# 7_Halleffec.net
KiCad netlist of a schematic drawn in Altium Designer
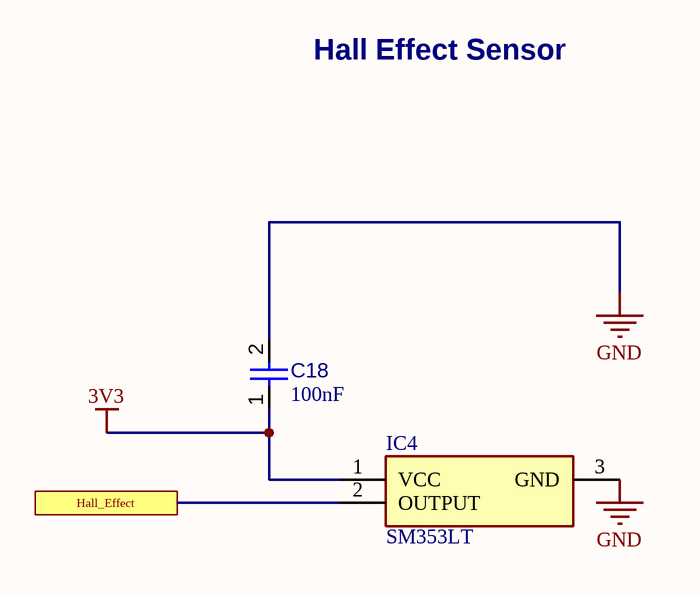
[diagram p0: [7]Halleffec.SchDoc]

(export (version "E")
  (design (tool "Eeschema 10.0.6"))
  (components
    (comp (ref "C18")
      (value "100nF")
      (footprint "CAPC1608X90X40ML10T20")
      (description "Chip Capacitor, 100 nF, +/- 10%, 50 V, 0603 (1608 Metric)")
      (fields (field (name "TOLERANCE") "10%") (field (name "Comment") "Capacitor 100 nF +/-10% 50 V 0603"))
      (libsource (lib "Latium Technologies") (part "CAP-NP-2"))
    )
    (comp (ref "IC4")
      (value "SM353LT")
      (footprint "SOT95P280X145-3N")
      (description "Integrated Circuit")
      (fields (field (name "MOUSER PART NUMBER") "785-SM353LT"))
      (libsource (lib "PCB_High_Voltage_Sensor") (part "SM353LT"))
    )
  )
  (nets
    (net (code "1") (name "/Hall_Effect") (class "Default")
      (node (ref "IC4") (pin "2") (pinfunction "OUTPUT_2") (pintype "passive"))
    )
    (net (code "2") (name "3V3") (class "Default")
      (node (ref "C18") (pin "1") (pinfunction "1_1") (pintype "passive"))
      (node (ref "IC4") (pin "1") (pinfunction "VCC_1") (pintype "passive"))
    )
    (net (code "3") (name "GND") (class "Default")
      (node (ref "C18") (pin "2") (pinfunction "2_2") (pintype "passive"))
      (node (ref "IC4") (pin "3") (pinfunction "GND_3") (pintype "passive"))
    )
  )
)
